# P3V3_PP5V_GESTION.net
KiCad netlist of a schematic drawn in Altium Designer
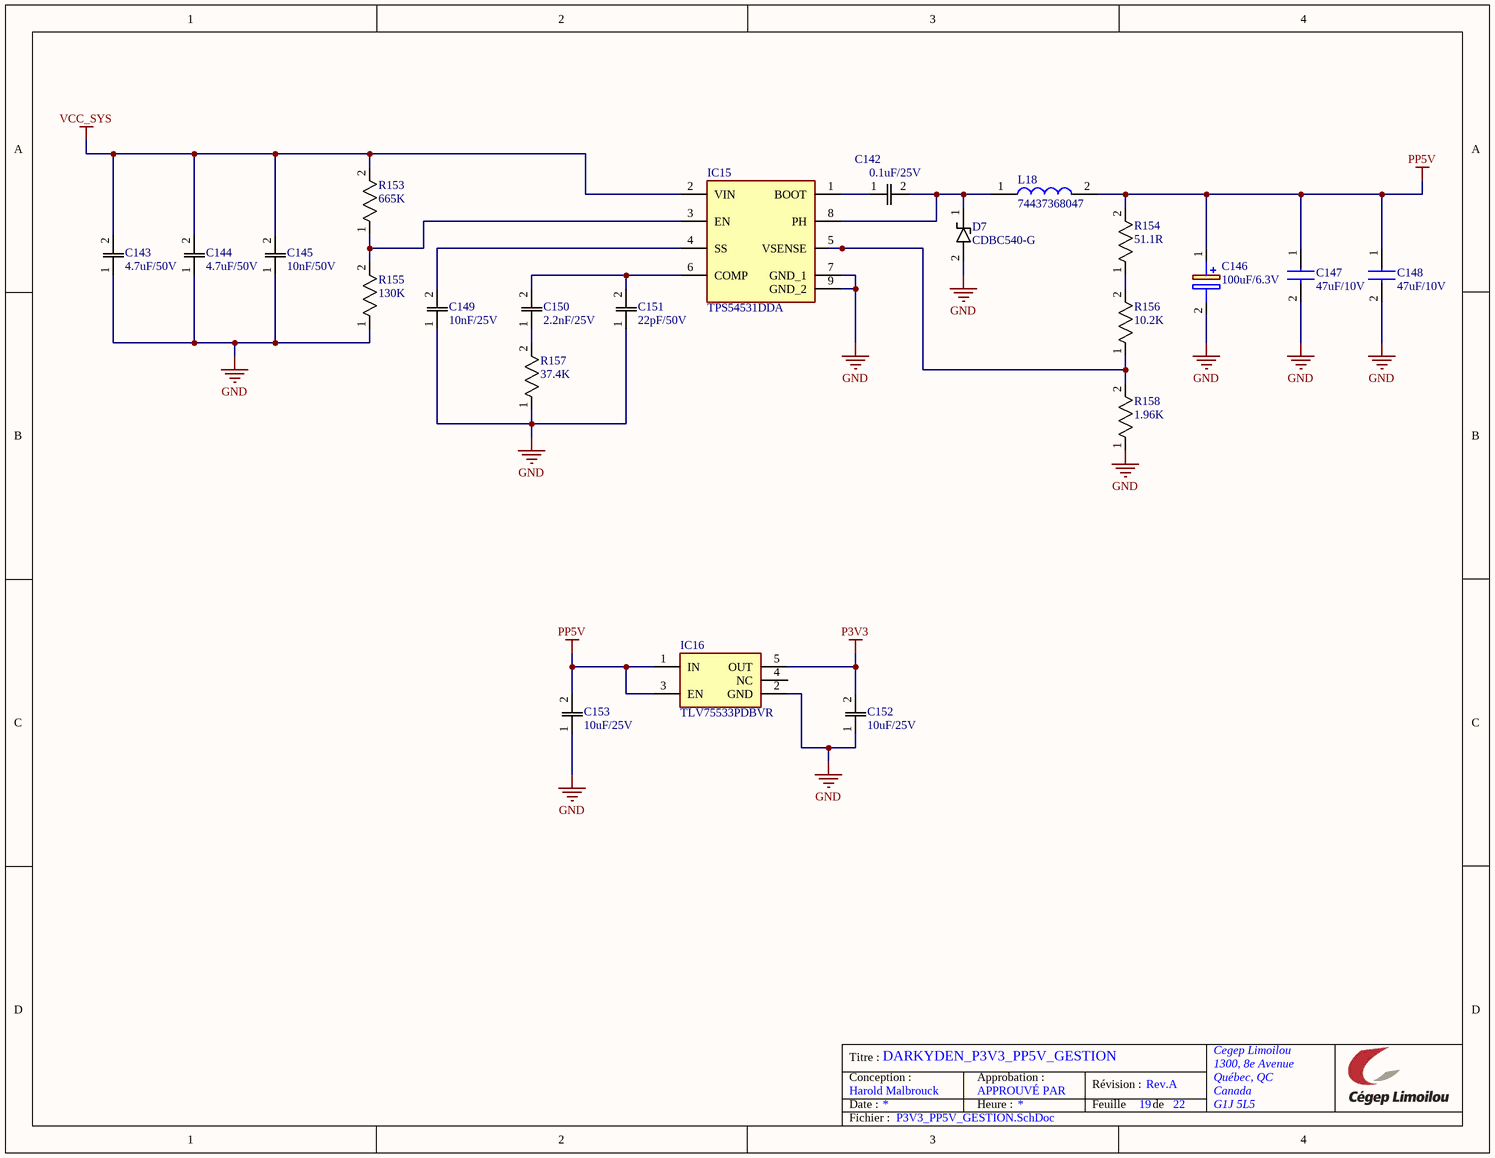
[diagram p0: P3V3_PP5V_GESTION.SchDoc]

(export (version "E")
  (design (tool "Eeschema 10.0.6"))
  (components
    (comp (ref "C142")
      (value "0.1uF/25V")
      (footprint "CAPC220145_88N_KEM")
      (description "0.1uF 25V X7R 10% SMD 0805 125C Plastic T/R")
      (fields
        (field (name "MANUFACTURER") "KEMET")
        (field (name "MANUFACTURER PART NUMBER") "C0805C104K3RACTU")
      )
      (libsource (lib "C0805C104K3RACTU") (part "C0805C104K3RACTU"))
    )
    (comp (ref "C143")
      (value "4.7uF/50V")
      (footprint "CGA4J3X5R1H475K125AB:CAP_2012_TDK")
      (description "4.7uF/50V X5R 卤10% 0805 Multilayer Ceramic Capacitors MLCC - SMD/SMT ROHS")
      (fields
        (field (name "MANUFACTURER") "TDK")
        (field (name "MANUFACTURER PART NUMBER") "CGA4J3X5R1H475K125AB")
      )
      (libsource (lib "CGA4J3X5R1H475K125AB") (part "CGA4J3X5R1H475K125AB"))
    )
    (comp (ref "C144")
      (value "4.7uF/50V")
      (footprint "CGA4J3X5R1H475K125AB:CAP_2012_TDK")
      (description "4.7uF/50V X5R 卤10% 0805 Multilayer Ceramic Capacitors MLCC - SMD/SMT ROHS")
      (fields
        (field (name "MANUFACTURER") "TDK")
        (field (name "MANUFACTURER PART NUMBER") "CGA4J3X5R1H475K125AB")
      )
      (libsource (lib "CGA4J3X5R1H475K125AB") (part "CGA4J3X5R1H475K125AB"))
    )
    (comp (ref "C145")
      (value "10nF/50V")
      (footprint "CAPC220145_88N_KEM")
      (description "10nF/50V X7R 0805 10%")
      (fields
        (field (name "MANUFACTURER") "KEMET")
        (field (name "MANUFACTURER PART NUMBER") "C0805C103K5RACTU")
      )
      (libsource (lib "C0805C103K5RACTU") (part "C0805C103K5RACTU"))
    )
    (comp (ref "C146")
      (value "100uF/6.3V")
      (footprint "SamacSys:T520B")
      (description "100uF / 6.3VDC B CASE 20%  Cap Tant Polymer SMD 3528-21 0.015 Ohm 105C T/R")
      (fields
        (field (name "MANUFACTURER_PART_NUMBER") "T520B107M006ATE015")
        (field (name "MOUSER PART NUMBER") "80-T520B107M6ATE15")
      )
      (libsource (lib "SamacSys") (part "T520B107M006ATE015"))
    )
    (comp (ref "C147")
      (value "47uF/10V")
      (footprint "SamacSys:CAPC3225X270N")
      (description "Multilayer Ceramic Capacitor, 47 uF, 10 V, ï¿½ 10%, X5R, 1210 [3225 Metric]")
      (fields
        (field (name "MANUFACTURER_PART_NUMBER") "GRM32ER61A476KE20L")
        (field (name "MOUSER PART NUMBER") "81-GRM32ER61A476KE20")
      )
      (libsource (lib "SamacSys") (part "GRM32ER61A476KE20L"))
    )
    (comp (ref "C148")
      (value "47uF/10V")
      (footprint "SamacSys:CAPC3225X270N")
      (description "Multilayer Ceramic Capacitor, 47 uF, 10 V, ï¿½ 10%, X5R, 1210 [3225 Metric]")
      (fields
        (field (name "MANUFACTURER_PART_NUMBER") "GRM32ER61A476KE20L")
        (field (name "MOUSER PART NUMBER") "81-GRM32ER61A476KE20")
      )
      (libsource (lib "SamacSys") (part "GRM32ER61A476KE20L"))
    )
    (comp (ref "C149")
      (value "10nF/25V")
      (footprint "SamacSys:C0805")
      (description "0.01uF 25V X7R 10% SMD 0805 125C Paper T/R")
      (fields
        (field (name "MANUFACTURER_PART_NUMBER") "C0805C103K3RACTU")
        (field (name "MOUSER PART NUMBER") "80-C0805C103K3R")
      )
      (libsource (lib "SamacSys") (part "C0805C103K3RACTU"))
    )
    (comp (ref "C150")
      (value "2.2nF/25V")
      (footprint "CAPC220145_88N_KEM")
      (description "2.2nF ±10% 25V Ceramic Capacitor C0G, NP0 0805 (2012 Metric)")
      (fields
        (field (name "MANUFACTURER") "KEMET")
        (field (name "MANUFACTURER PART NUMBER") "C0805C222K3GECTU")
      )
      (libsource (lib "C1812C222F1GACTU") (part "C0805C222K3GECTU"))
    )
    (comp (ref "C151")
      (value "22pF/50V")
      (footprint "CAPC220145_88N_KEM")
      (description "Cap Ceramic 22pF 50V X7R 5% Pad SMD 0805 125°C T/R")
      (fields
        (field (name "MANUFACTURER") "KEMET")
        (field (name "MANUFACTURER PART NUMBER") "C0805C220J5RACTU")
      )
      (libsource (lib "C0805C220J5RACTU") (part "C0805C220J5RACTU"))
    )
    (comp (ref "C152")
      (value "10uF/25V")
      (footprint "CAPC220145_88N_KEM")
      (description "10uF / 25 VDC, +85degC, X5R Dielec, +/-10% ¦ KEMET C0805C106K3PACTU 0805")
      (fields
        (field (name "MANUFACTURER") "KEMET")
        (field (name "MANUFACTURER PART NUMBER") "C0805C106K3PACTU")
      )
      (libsource (lib "C0805C106K3PACTU") (part "C0805C106K3PACTU"))
    )
    (comp (ref "C153")
      (value "10uF/25V")
      (footprint "CAPC220145_88N_KEM")
      (description "10uF / 25 VDC, +85degC, X5R Dielec, +/-10% ¦ KEMET C0805C106K3PACTU 0805")
      (fields
        (field (name "MANUFACTURER") "KEMET")
        (field (name "MANUFACTURER PART NUMBER") "C0805C106K3PACTU")
      )
      (libsource (lib "C0805C106K3PACTU") (part "C0805C106K3PACTU"))
    )
    (comp (ref "D7")
      (value "CDBC540-G")
      (footprint "SamacSys:DIOM8059X290N")
      (description "Schottky Diode 40V 5A 2-Pin DO-214AB (SMC) CDBC540-G SMT")
      (fields (field (name "MOUSER PART NUMBER") "750-CDBC540-G") (field (name "MANUFACTURER") "Comchip"))
      (libsource (lib "SamacSys") (part "CDBC540-G"))
    )
    (comp (ref "IC15")
      (value "TPS54531DDA")
      (footprint "SamacSys:SOIC127P600X170-9N")
      (fields (field (name "MOUSER PART NUMBER") "595-TPS54531DDA"))
      (libsource (lib "SamacSys") (part "TPS54531DDA"))
    )
    (comp (ref "IC16")
      (value "TLV75533PDBVR")
      (footprint "SamacSys:SOT95P280X145-5N")
      (description "500mA high-PSRR low-IQ low-dropout voltage regulator with enable 5-SOT-23 -40 to 125")
      (fields
        (field (name "MOUSER PART NUMBER") "595-TLV75533PDBVR")
        (field (name "MANUFACTURER") "Texas Instruments")
      )
      (libsource (lib "SamacSys") (part "TLV75533PDBVR"))
    )
    (comp (ref "L18")
      (value "74437368047")
      (footprint "SamacSys:WE-LHMI_104048")
      (fields
        (field (name "MOUSER PART NUMBER") "710-74437368047")
        (field (name "MANUFACTURER") "Wurth Electronics")
        (field (name "TOLERANCE") "20%")
      )
      (libsource (lib "SamacSys") (part "74437368047"))
    )
    (comp (ref "R153")
      (value "665K")
      (footprint "RC0603N_PAN")
      (description "665 kOhm, ± 1%, 100 mW, 0603 [1608 Metric], Thick Film, Precision")
      (fields
        (field (name "MANUFACTURER") "Panasonic")
        (field (name "MANUFACTURER PART NUMBER") "ERJ-3EKF6653V")
      )
      (libsource (lib "ERJ-3EKF6653V") (part "ERJ-3EKF6653V"))
    )
    (comp (ref "R154")
      (value "51.1R")
      (footprint "SamacSys:RESC1608X55N")
      (description "51.1 Ohm 1% 0.1W(1/10W) ±100ppm/C Pad SMD T/R Automotive AEC-Q200")
      (fields
        (field (name "MANUFACTURER_PART_NUMBER") "ERJ-3EKF51R1V")
        (field (name "MOUSER PART NUMBER") "667-ERJ-3EKF51R1V")
      )
      (libsource (lib "SamacSys") (part "ERJ-3EKF51R1V"))
    )
    (comp (ref "R155")
      (value "130K")
      (footprint "RC0603N_PAN")
      (description "130K Ohm 1% 0.1W Res Thick Film 0603 ±100ppm/°C Molded SMD Punched Carrier T/R")
      (fields
        (field (name "MANUFACTURER") "Panasonic")
        (field (name "MANUFACTURER PART NUMBER") "ERJ-3EKF1303V")
      )
      (libsource (lib "ERJ-3EKF1303V") (part "ERJ-3EKF1303V"))
    )
    (comp (ref "R156")
      (value "10.2K")
      (footprint "SamacSys:RESC1608X55N")
      (description "10.2 kOhm, ± 1%, 100 mW, 0603 [1608 Metric], Thick Film, Precision")
      (fields
        (field (name "MANUFACTURER_PART_NUMBER") "ERJ-3EKF1022V")
        (field (name "MOUSER PART NUMBER") "667-ERJ-3EKF1022V")
      )
      (libsource (lib "SamacSys") (part "ERJ-3EKF1022V"))
    )
    (comp (ref "R157")
      (value "37.4K")
      (footprint "RC0603N_PAN")
      (description "37.4K Ohm 1% 1/10W ±100ppm/°C Molded SMD Punched Carrier T/R")
      (fields
        (field (name "MANUFACTURER") "Panasonic")
        (field (name "MANUFACTURER PART NUMBER") "ERJ-3EKF3742V")
      )
      (libsource (lib "ERJ-3EKF3742V") (part "ERJ-3EKF3742V"))
    )
    (comp (ref "R158")
      (value "1.96K")
      (footprint "RC0603N_PAN")
      (description "1.96K Ohm 1% 1/10W ±100ppm/°C Molded SMD Punched Carrier T/R")
      (fields
        (field (name "MANUFACTURER") "Panasonic")
        (field (name "MANUFACTURER PART NUMBER") "ERJ-3EKF1961V")
      )
      (libsource (lib "ERJ-3EKF1961V") (part "ERJ-3EKF1961V"))
    )
  )
  (nets
    (net (code "1") (name "GND") (class "Default")
      (node (ref "C143") (pin "1") (pinfunction "1_1") (pintype "passive"))
      (node (ref "C144") (pin "1") (pinfunction "1_1") (pintype "passive"))
      (node (ref "C145") (pin "1") (pinfunction "1_1") (pintype "passive"))
      (node (ref "C146") (pin "2") (pinfunction "-_2") (pintype "passive"))
      (node (ref "C147") (pin "2") (pinfunction "2_2") (pintype "passive"))
      (node (ref "C148") (pin "2") (pinfunction "2_2") (pintype "passive"))
      (node (ref "C149") (pin "1") (pinfunction "1_1") (pintype "passive"))
      (node (ref "C151") (pin "1") (pinfunction "1_1") (pintype "passive"))
      (node (ref "C152") (pin "1") (pinfunction "1_1") (pintype "passive"))
      (node (ref "C153") (pin "1") (pinfunction "1_1") (pintype "passive"))
      (node (ref "D7") (pin "2") (pinfunction "A_2") (pintype "passive"))
      (node (ref "IC15") (pin "7") (pinfunction "GND_1_7") (pintype "passive"))
      (node (ref "IC15") (pin "9") (pinfunction "GND_2_9") (pintype "passive"))
      (node (ref "IC16") (pin "2") (pinfunction "GND_2") (pintype "passive"))
      (node (ref "R155") (pin "1") (pinfunction "1_1") (pintype "passive"))
      (node (ref "R157") (pin "1") (pinfunction "1_1") (pintype "passive"))
      (node (ref "R158") (pin "1") (pinfunction "1_1") (pintype "passive"))
    )
    (net (code "2") (name "Net-(C150-Pad1)") (class "Default")
      (node (ref "C150") (pin "1") (pinfunction "1_1") (pintype "passive"))
      (node (ref "R157") (pin "2") (pinfunction "2_2") (pintype "passive"))
    )
    (net (code "3") (name "Net-(D7-K)") (class "Default")
      (node (ref "C142") (pin "2") (pinfunction "2_2") (pintype "passive"))
      (node (ref "D7") (pin "1") (pinfunction "K_1") (pintype "passive"))
      (node (ref "IC15") (pin "8") (pinfunction "PH_8") (pintype "passive"))
      (node (ref "L18") (pin "1") (pinfunction "1_1") (pintype "passive"))
    )
    (net (code "4") (name "Net-(IC15-BOOT)") (class "Default")
      (node (ref "C142") (pin "1") (pinfunction "1_1") (pintype "passive"))
      (node (ref "IC15") (pin "1") (pinfunction "BOOT_1") (pintype "passive"))
    )
    (net (code "5") (name "Net-(IC15-COMP)") (class "Default")
      (node (ref "C150") (pin "2") (pinfunction "2_2") (pintype "passive"))
      (node (ref "C151") (pin "2") (pinfunction "2_2") (pintype "passive"))
      (node (ref "IC15") (pin "6") (pinfunction "COMP_6") (pintype "passive"))
    )
    (net (code "6") (name "Net-(IC15-EN)") (class "Default")
      (node (ref "IC15") (pin "3") (pinfunction "EN_3") (pintype "passive"))
      (node (ref "R153") (pin "1") (pinfunction "1_1") (pintype "passive"))
      (node (ref "R155") (pin "2") (pinfunction "2_2") (pintype "passive"))
    )
    (net (code "7") (name "Net-(IC15-SS)") (class "Default")
      (node (ref "C149") (pin "2") (pinfunction "2_2") (pintype "passive"))
      (node (ref "IC15") (pin "4") (pinfunction "SS_4") (pintype "passive"))
    )
    (net (code "8") (name "Net-(IC15-VSENSE)") (class "Default")
      (node (ref "IC15") (pin "5") (pinfunction "VSENSE_5") (pintype "passive"))
      (node (ref "R156") (pin "1") (pinfunction "1_1") (pintype "passive"))
      (node (ref "R158") (pin "2") (pinfunction "2_2") (pintype "passive"))
    )
    (net (code "9") (name "Net-(R154-Pad1)") (class "Default")
      (node (ref "R154") (pin "1") (pinfunction "1_1") (pintype "passive"))
      (node (ref "R156") (pin "2") (pinfunction "2_2") (pintype "passive"))
    )
    (net (code "10") (name "P3V3") (class "Default")
      (node (ref "C152") (pin "2") (pinfunction "2_2") (pintype "passive"))
      (node (ref "IC16") (pin "5") (pinfunction "OUT_5") (pintype "passive"))
    )
    (net (code "11") (name "PP5V") (class "Default")
      (node (ref "C146") (pin "1") (pinfunction "+_1") (pintype "passive"))
      (node (ref "C147") (pin "1") (pinfunction "1_1") (pintype "passive"))
      (node (ref "C148") (pin "1") (pinfunction "1_1") (pintype "passive"))
      (node (ref "C153") (pin "2") (pinfunction "2_2") (pintype "passive"))
      (node (ref "IC16") (pin "1") (pinfunction "IN_1") (pintype "passive"))
      (node (ref "IC16") (pin "3") (pinfunction "EN_3") (pintype "passive"))
      (node (ref "L18") (pin "2") (pinfunction "2_2") (pintype "passive"))
      (node (ref "R154") (pin "2") (pinfunction "2_2") (pintype "passive"))
    )
    (net (code "12") (name "VCC_SYS") (class "Default")
      (node (ref "C143") (pin "2") (pinfunction "2_2") (pintype "passive"))
      (node (ref "C144") (pin "2") (pinfunction "2_2") (pintype "passive"))
      (node (ref "C145") (pin "2") (pinfunction "2_2") (pintype "passive"))
      (node (ref "IC15") (pin "2") (pinfunction "VIN_2") (pintype "passive"))
      (node (ref "R153") (pin "2") (pinfunction "2_2") (pintype "passive"))
    )
    (net (code "13") (name "unconnected-(IC16-NC-Pad4)") (class "Default")
      (node (ref "IC16") (pin "4") (pinfunction "NC_4") (pintype "passive"))
    )
  )
)
